# New_SERV_OPEN8_SOTB.net
KiCad netlist of a schematic drawn in EAGLE
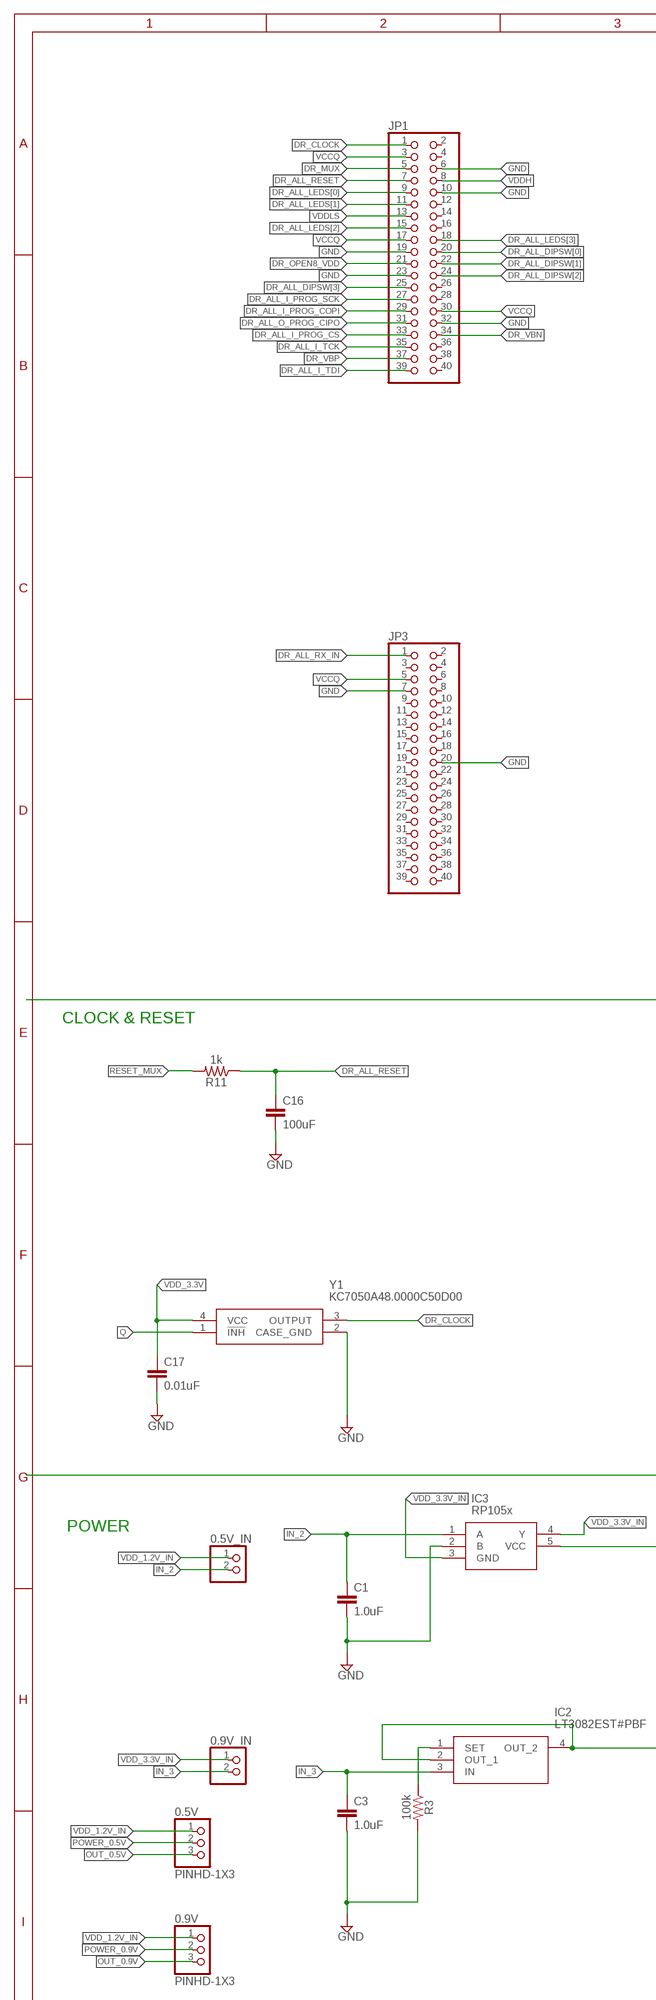
[diagram p0: schematic, sheet 1, part 1 of 2]
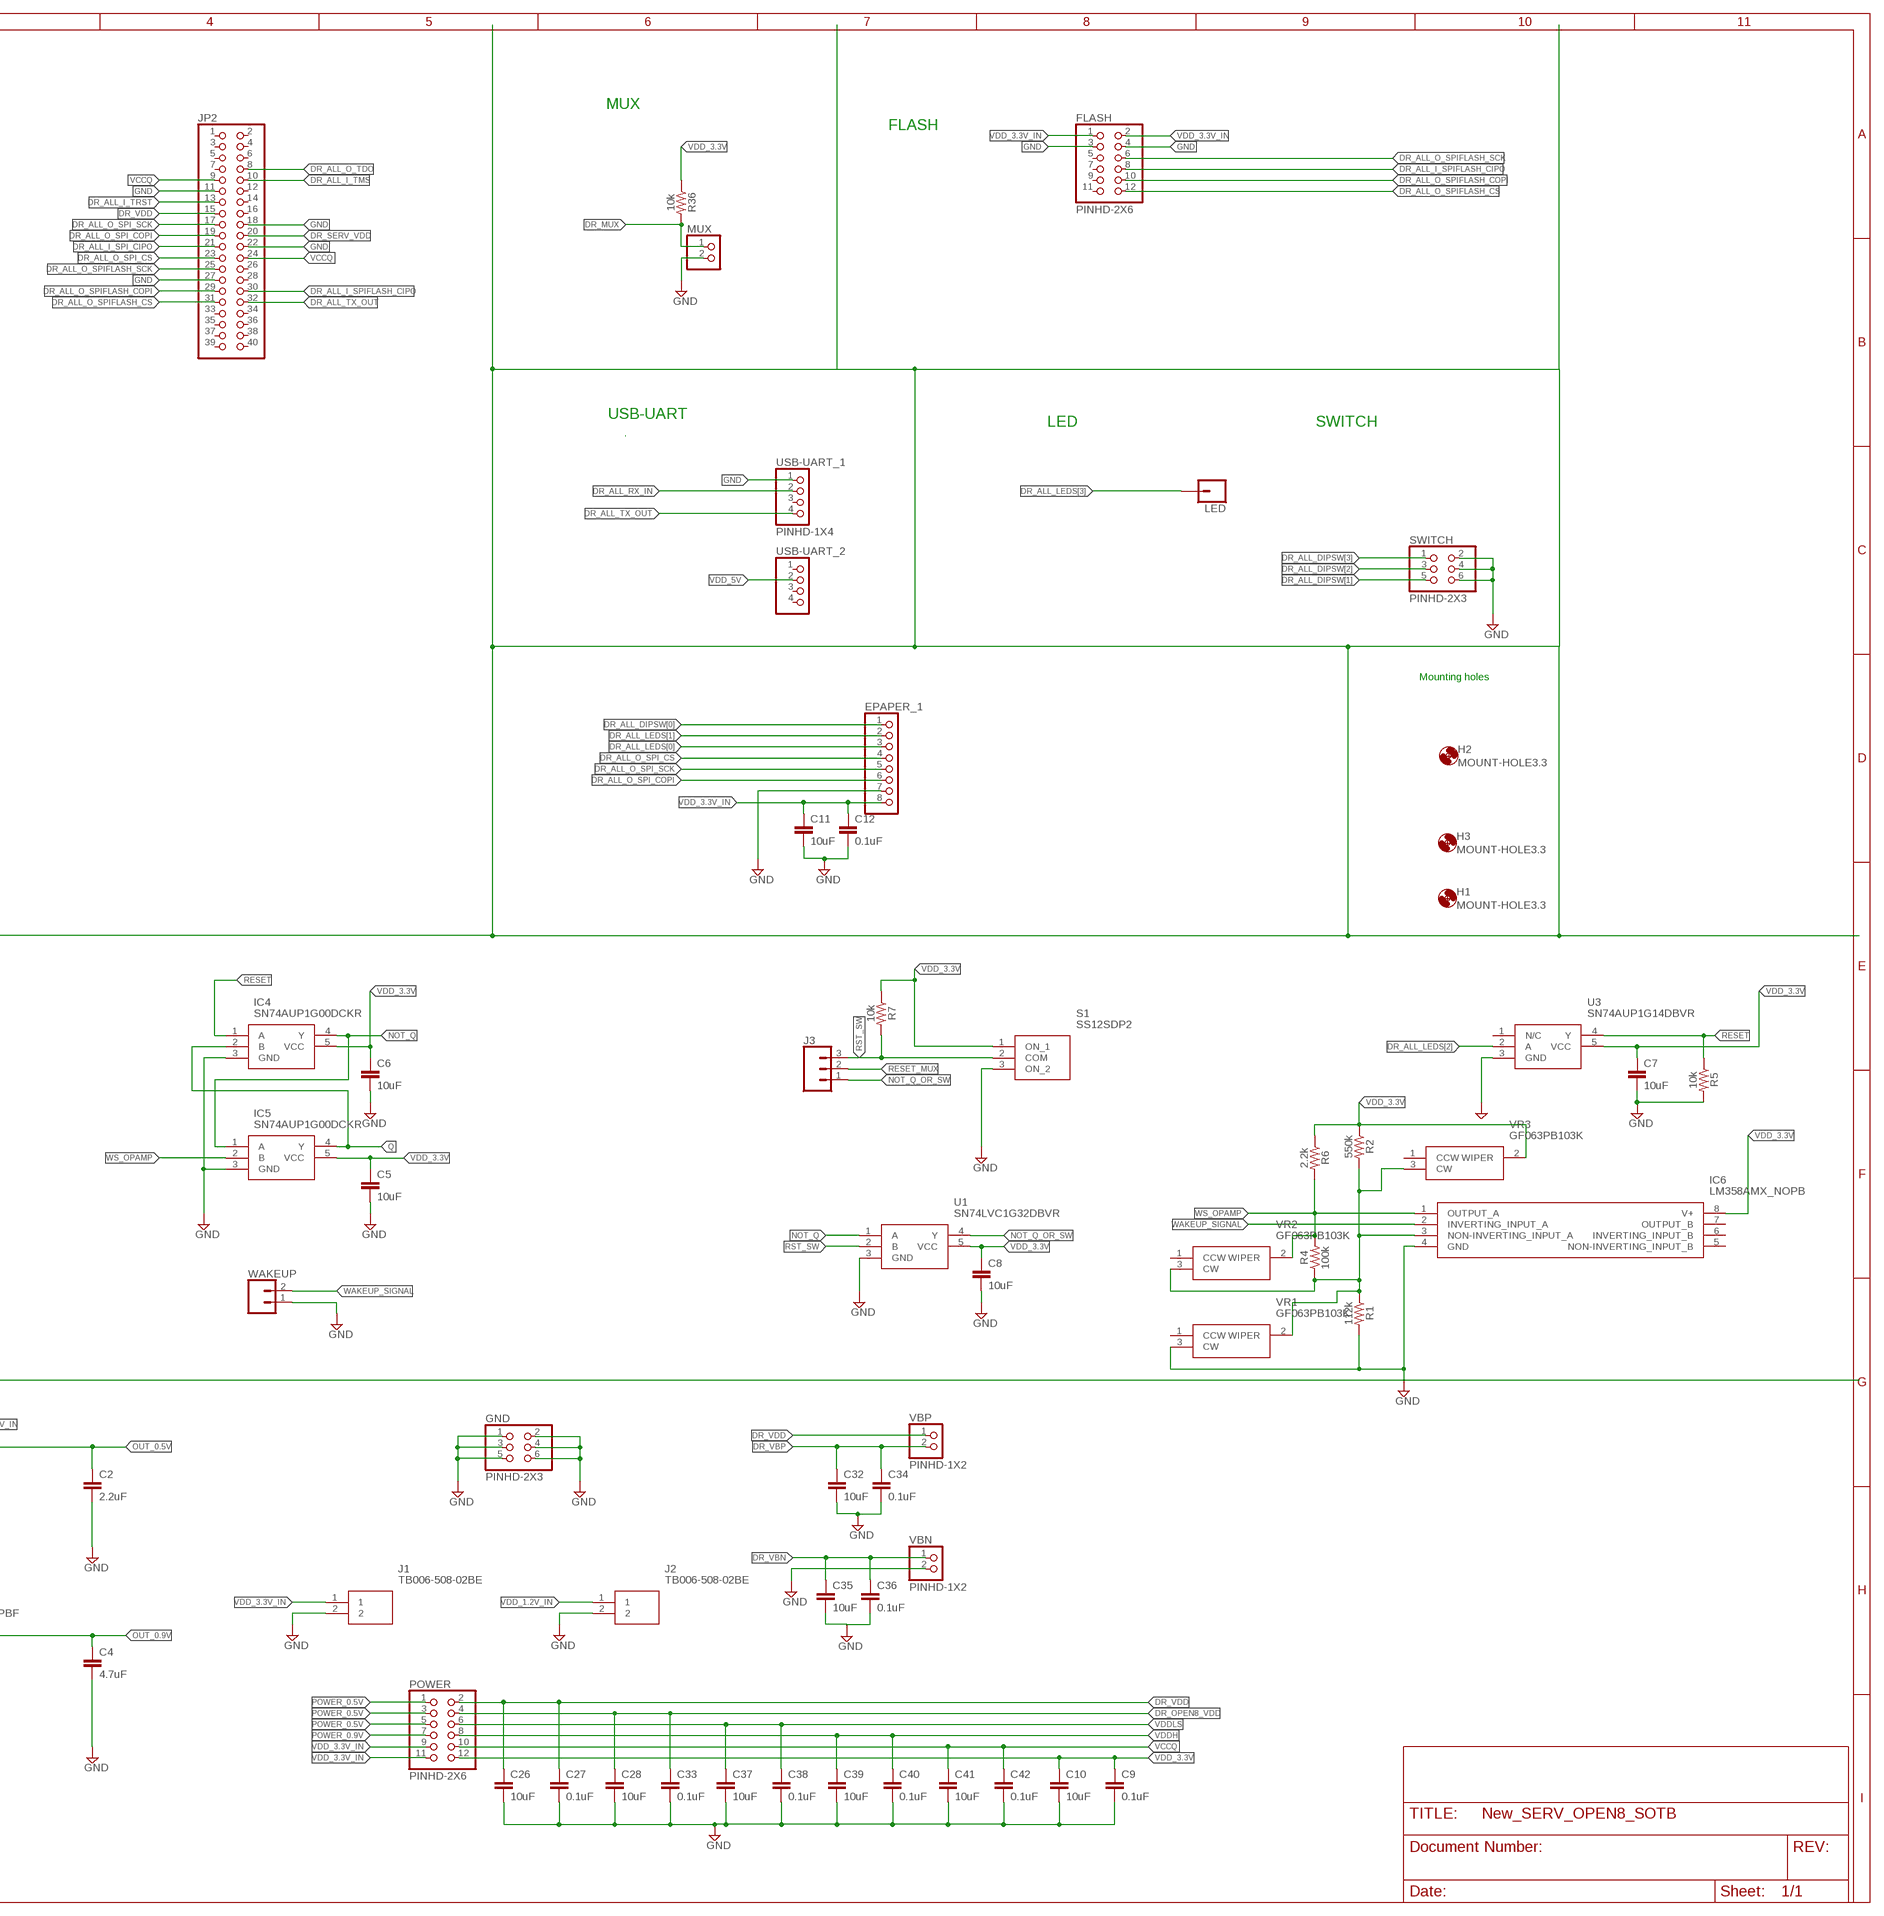
[diagram p1: schematic, sheet 1, part 2 of 2]

(export (version "E")
  (design (tool "Eeschema 10.0.6"))
  (components
    (comp (ref "0.5V")
      (value "PINHD-1X3")
      (footprint "eagle-import:1X03")
      (libsource (lib "eagle-import") (part "PINHD-1X3"))
    )
    (comp (ref "0.5V_IN")
      (value "PINHD-1X2")
      (footprint "eagle-import:1X02")
      (libsource (lib "eagle-import") (part "pinhead_325_PINHD-1X2"))
    )
    (comp (ref "0.9V")
      (value "PINHD-1X3")
      (footprint "eagle-import:1X03")
      (libsource (lib "eagle-import") (part "PINHD-1X3"))
    )
    (comp (ref "0.9V_IN")
      (value "PINHD-1X2")
      (footprint "eagle-import:1X02")
      (libsource (lib "eagle-import") (part "pinhead_325_PINHD-1X2"))
    )
    (comp (ref "C1")
      (value "1.0uF")
      (footprint "eagle-import:0805")
      (libsource (lib "eagle-import") (part "1.0UF-0805-25V-(+80/-20%)"))
    )
    (comp (ref "C2")
      (value "2.2uF")
      (footprint "eagle-import:0805")
      (libsource (lib "eagle-import") (part "1.0UF-0805-25V-(+80/-20%)"))
    )
    (comp (ref "C3")
      (value "1.0uF")
      (footprint "eagle-import:0805")
      (libsource (lib "eagle-import") (part "1.0UF-0805-25V-(+80/-20%)"))
    )
    (comp (ref "C4")
      (value "4.7uF")
      (footprint "eagle-import:0805")
      (libsource (lib "eagle-import") (part "1.0UF-0805-25V-(+80/-20%)"))
    )
    (comp (ref "C5")
      (value "10uF")
      (footprint "eagle-import:0805")
      (libsource (lib "eagle-import") (part "1.0UF-0805-25V-(+80/-20%)"))
    )
    (comp (ref "C6")
      (value "10uF")
      (footprint "eagle-import:0805")
      (libsource (lib "eagle-import") (part "1.0UF-0805-25V-(+80/-20%)"))
    )
    (comp (ref "C7")
      (value "10uF")
      (footprint "eagle-import:0805")
      (libsource (lib "eagle-import") (part "1.0UF-0805-25V-(+80/-20%)"))
    )
    (comp (ref "C8")
      (value "10uF")
      (footprint "eagle-import:0805")
      (libsource (lib "eagle-import") (part "1.0UF-0805-25V-(+80/-20%)"))
    )
    (comp (ref "C9")
      (value "0.1uF")
      (footprint "eagle-import:0805")
      (libsource (lib "eagle-import") (part "1.0UF-0805-25V-(+80/-20%)"))
    )
    (comp (ref "C10")
      (value "10uF")
      (footprint "eagle-import:0805")
      (libsource (lib "eagle-import") (part "1.0UF-0805-25V-(+80/-20%)"))
    )
    (comp (ref "C11")
      (value "10uF")
      (footprint "eagle-import:0805")
      (libsource (lib "eagle-import") (part "1.0UF-0805-25V-(+80/-20%)"))
    )
    (comp (ref "C12")
      (value "0.1uF")
      (footprint "eagle-import:0805")
      (libsource (lib "eagle-import") (part "1.0UF-0805-25V-(+80/-20%)"))
    )
    (comp (ref "C16")
      (value "100uF")
      (footprint "eagle-import:0805")
      (libsource (lib "eagle-import") (part "1.0UF-0805-25V-(+80/-20%)"))
    )
    (comp (ref "C17")
      (value "0.01uF")
      (footprint "eagle-import:0805")
      (libsource (lib "eagle-import") (part "1.0UF-0805-25V-(+80/-20%)"))
    )
    (comp (ref "C26")
      (value "10uF")
      (footprint "eagle-import:0805")
      (libsource (lib "eagle-import") (part "1.0UF-0805-25V-(+80/-20%)"))
    )
    (comp (ref "C27")
      (value "0.1uF")
      (footprint "eagle-import:0805")
      (libsource (lib "eagle-import") (part "1.0UF-0805-25V-(+80/-20%)"))
    )
    (comp (ref "C28")
      (value "10uF")
      (footprint "eagle-import:0805")
      (libsource (lib "eagle-import") (part "1.0UF-0805-25V-(+80/-20%)"))
    )
    (comp (ref "C32")
      (value "10uF")
      (footprint "eagle-import:0805")
      (libsource (lib "eagle-import") (part "1.0UF-0805-25V-(+80/-20%)"))
    )
    (comp (ref "C33")
      (value "0.1uF")
      (footprint "eagle-import:0805")
      (libsource (lib "eagle-import") (part "1.0UF-0805-25V-(+80/-20%)"))
    )
    (comp (ref "C34")
      (value "0.1uF")
      (footprint "eagle-import:0805")
      (libsource (lib "eagle-import") (part "1.0UF-0805-25V-(+80/-20%)"))
    )
    (comp (ref "C35")
      (value "10uF")
      (footprint "eagle-import:0805")
      (libsource (lib "eagle-import") (part "1.0UF-0805-25V-(+80/-20%)"))
    )
    (comp (ref "C36")
      (value "0.1uF")
      (footprint "eagle-import:0805")
      (libsource (lib "eagle-import") (part "1.0UF-0805-25V-(+80/-20%)"))
    )
    (comp (ref "C37")
      (value "10uF")
      (footprint "eagle-import:0805")
      (libsource (lib "eagle-import") (part "1.0UF-0805-25V-(+80/-20%)"))
    )
    (comp (ref "C38")
      (value "0.1uF")
      (footprint "eagle-import:0805")
      (libsource (lib "eagle-import") (part "1.0UF-0805-25V-(+80/-20%)"))
    )
    (comp (ref "C39")
      (value "10uF")
      (footprint "eagle-import:0805")
      (libsource (lib "eagle-import") (part "1.0UF-0805-25V-(+80/-20%)"))
    )
    (comp (ref "C40")
      (value "0.1uF")
      (footprint "eagle-import:0805")
      (libsource (lib "eagle-import") (part "1.0UF-0805-25V-(+80/-20%)"))
    )
    (comp (ref "C41")
      (value "10uF")
      (footprint "eagle-import:0805")
      (libsource (lib "eagle-import") (part "1.0UF-0805-25V-(+80/-20%)"))
    )
    (comp (ref "C42")
      (value "0.1uF")
      (footprint "eagle-import:0805")
      (libsource (lib "eagle-import") (part "1.0UF-0805-25V-(+80/-20%)"))
    )
    (comp (ref "EPAPER_1")
      (value "PINHD-1X8")
      (footprint "eagle-import:1X08")
      (libsource (lib "eagle-import") (part "PINHD-1X8"))
    )
    (comp (ref "FLASH")
      (value "PINHD-2X6")
      (footprint "eagle-import:2X06")
      (libsource (lib "eagle-import") (part "PINHD-2X6"))
    )
    (comp (ref "GND")
      (value "PINHD-2X3")
      (footprint "eagle-import:2X03")
      (libsource (lib "eagle-import") (part "PINHD-2X3"))
    )
    (comp (ref "H1")
      (value "MOUNT-HOLE3.3")
      (footprint "eagle-import:3,3")
      (libsource (lib "eagle-import") (part "MOUNT-HOLE3.3"))
    )
    (comp (ref "H2")
      (value "MOUNT-HOLE3.3")
      (footprint "eagle-import:3,3")
      (libsource (lib "eagle-import") (part "MOUNT-HOLE3.3"))
    )
    (comp (ref "H3")
      (value "MOUNT-HOLE3.3")
      (footprint "eagle-import:3,3")
      (libsource (lib "eagle-import") (part "MOUNT-HOLE3.3"))
    )
    (comp (ref "IC2")
      (value "LT3082EST#PBF")
      (footprint "eagle-import:SOT230P700X180-4N")
      (fields (field (name "MOUSER_PART_NUMBER") "584-LT3082EST#PBF"))
      (libsource (lib "eagle-import") (part "LT3082EST#PBF"))
    )
    (comp (ref "IC3")
      (value "RP105x")
      (footprint "eagle-import:SOT95P280X145-5N")
      (fields
        (field (name "ARROW_PART_NUMBER") "SN74LVC1G32DBVR")
        (field (name "MOUSER_PART_NUMBER") "595-SN74LVC1G32DBVR")
      )
      (libsource (lib "eagle-import") (part "SN74LVC1G32DBVR"))
    )
    (comp (ref "IC4")
      (value "SN74AUP1G00DCKR")
      (footprint "eagle-import:SOT65P210X110-5N")
      (fields (field (name "MOUSER_PART_NUMBER") "595-SN74AUP1G00DCKR"))
      (libsource (lib "eagle-import") (part "SN74AUP1G00DCKR"))
    )
    (comp (ref "IC5")
      (value "SN74AUP1G00DCKR")
      (footprint "eagle-import:SOT65P210X110-5N")
      (fields (field (name "MOUSER_PART_NUMBER") "595-SN74AUP1G00DCKR"))
      (libsource (lib "eagle-import") (part "SN74AUP1G00DCKR"))
    )
    (comp (ref "IC6")
      (value "LM358AMX_NOPB")
      (footprint "eagle-import:SOIC127P600X175-8N")
      (fields
        (field (name "ARROW_PART_NUMBER") "LM358AMX/NOPB")
        (field (name "MOUSER_PART_NUMBER") "926-LM358AMX/NOPB")
      )
      (libsource (lib "eagle-import") (part "LM358AMX_NOPB"))
    )
    (comp (ref "J1")
      (value "TB006-508-02BE")
      (footprint "eagle-import:TB00650802BE")
      (fields (field (name "MOUSER_PART_NUMBER") "490-TB006-508-02BE"))
      (libsource (lib "eagle-import") (part "TB006-508-02BE"))
    )
    (comp (ref "J2")
      (value "TB006-508-02BE")
      (footprint "eagle-import:TB00650802BE")
      (fields (field (name "MOUSER_PART_NUMBER") "490-TB006-508-02BE"))
      (libsource (lib "eagle-import") (part "TB006-508-02BE"))
    )
    (comp (ref "J3")
      (value "CONN_03")
      (footprint "eagle-import:1X03")
      (libsource (lib "eagle-import") (part "CONN_03"))
    )
    (comp (ref "JP1")
      (value "PINHD-2X20")
      (footprint "eagle-import:2X20")
      (libsource (lib "eagle-import") (part "PINHD-2X20"))
    )
    (comp (ref "JP2")
      (value "PINHD-2X20")
      (footprint "eagle-import:2X20")
      (libsource (lib "eagle-import") (part "PINHD-2X20"))
    )
    (comp (ref "JP3")
      (value "PINHD-2X20")
      (footprint "eagle-import:2X20")
      (libsource (lib "eagle-import") (part "PINHD-2X20"))
    )
    (comp (ref "LED")
      (value "CONN_01")
      (footprint "eagle-import:1X01")
      (libsource (lib "eagle-import") (part "CONN_01"))
    )
    (comp (ref "MUX")
      (value "PINHD-1X2")
      (footprint "eagle-import:1X02")
      (libsource (lib "eagle-import") (part "pinhead_325_PINHD-1X2"))
    )
    (comp (ref "POWER")
      (value "PINHD-2X6")
      (footprint "eagle-import:2X06")
      (libsource (lib "eagle-import") (part "PINHD-2X6"))
    )
    (comp (ref "R1")
      (value "112k")
      (footprint "eagle-import:0805")
      (libsource (lib "eagle-import") (part "0.3OHM-0805-1/8W-1%"))
    )
    (comp (ref "R2")
      (value "550k")
      (footprint "eagle-import:0805")
      (libsource (lib "eagle-import") (part "0.3OHM-0805-1/8W-1%"))
    )
    (comp (ref "R3")
      (value "100k")
      (footprint "eagle-import:0805")
      (libsource (lib "eagle-import") (part "0.3OHM-0805-1/8W-1%"))
    )
    (comp (ref "R4")
      (value "100k")
      (footprint "eagle-import:0805")
      (libsource (lib "eagle-import") (part "0.3OHM-0805-1/8W-1%"))
    )
    (comp (ref "R5")
      (value "10k")
      (footprint "eagle-import:0805")
      (libsource (lib "eagle-import") (part "0.3OHM-0805-1/8W-1%"))
    )
    (comp (ref "R6")
      (value "2.2k")
      (footprint "eagle-import:0805")
      (libsource (lib "eagle-import") (part "0.3OHM-0805-1/8W-1%"))
    )
    (comp (ref "R7")
      (value "10k")
      (footprint "eagle-import:0805")
      (libsource (lib "eagle-import") (part "0.3OHM-0805-1/8W-1%"))
    )
    (comp (ref "R11")
      (value "1k")
      (footprint "eagle-import:0805")
      (libsource (lib "eagle-import") (part "0.3OHM-0805-1/8W-1%"))
    )
    (comp (ref "R36")
      (value "10k")
      (footprint "eagle-import:0805")
      (libsource (lib "eagle-import") (part "0.3OHM-0805-1/8W-1%"))
    )
    (comp (ref "S1")
      (value "SS12SDP2")
      (footprint "eagle-import:SS12SDP2")
      (fields (field (name "MOUSER_PART_NUMBER") "633-SS12SDP2"))
      (libsource (lib "eagle-import") (part "SS12SDP2"))
    )
    (comp (ref "SWITCH")
      (value "PINHD-2X3")
      (footprint "eagle-import:2X03")
      (libsource (lib "eagle-import") (part "PINHD-2X3"))
    )
    (comp (ref "U1")
      (value "SN74LVC1G32DBVR")
      (footprint "eagle-import:SOT95P280X145-5N")
      (fields (field (name "MOUSER_PART_NUMBER") "595-SN74LVC1G32DBVR"))
      (libsource (lib "eagle-import") (part "SN74LVC1G32DBVR"))
    )
    (comp (ref "U3")
      (value "SN74AUP1G14DBVR")
      (footprint "eagle-import:SOT65P210X110-5N")
      (fields (field (name "MOUSER_PART_NUMBER") "595-SN74AUP1G14DBVR"))
      (libsource (lib "eagle-import") (part "SN74AUP1G14DBVR"))
    )
    (comp (ref "USB-UART_1")
      (value "PINHD-1X4")
      (footprint "eagle-import:1X04")
      (libsource (lib "eagle-import") (part "PINHD-1X4"))
    )
    (comp (ref "USB-UART_2")
      (value "PINHD-1X4")
      (footprint "eagle-import:1X04")
      (libsource (lib "eagle-import") (part "PINHD-1X4"))
    )
    (comp (ref "VBN")
      (value "PINHD-1X2")
      (footprint "eagle-import:1X02")
      (libsource (lib "eagle-import") (part "PINHD-1X2"))
    )
    (comp (ref "VBP")
      (value "PINHD-1X2")
      (footprint "eagle-import:1X02")
      (libsource (lib "eagle-import") (part "PINHD-1X2"))
    )
    (comp (ref "VR1")
      (value "GF063PB103K")
      (footprint "eagle-import:GF063PB103K")
      (libsource (lib "eagle-import") (part "GF063PB103K"))
    )
    (comp (ref "VR2")
      (value "GF063PB103K")
      (footprint "eagle-import:GF063PB103K")
      (libsource (lib "eagle-import") (part "GF063PB103K"))
    )
    (comp (ref "VR3")
      (value "GF063PB103K")
      (footprint "eagle-import:GF063PB103K")
      (libsource (lib "eagle-import") (part "GF063PB103K"))
    )
    (comp (ref "WAKEUP")
      (value "CONN_02")
      (footprint "eagle-import:1X02")
      (libsource (lib "eagle-import") (part "CONN_02"))
    )
    (comp (ref "Y1")
      (value "KC7050A48.0000C50D00")
      (footprint "eagle-import:KC7050A480000C50D00")
      (fields (field (name "MOUSER_PART_NUMBER") "581-KC7050A48C50D"))
      (libsource (lib "eagle-import") (part "KC7050A48.0000C50D00"))
    )
  )
  (nets
    (net (code "1") (name "DR_ALL_DIPSW[0]") (class "Default")
      (node (ref "EPAPER_1") (pin "1") (pinfunction "1_1") (pintype "passive"))
      (node (ref "JP1") (pin "20") (pinfunction "20_20") (pintype "passive"))
    )
    (net (code "2") (name "DR_ALL_DIPSW[1]") (class "Default")
      (node (ref "JP1") (pin "22") (pinfunction "22_22") (pintype "passive"))
      (node (ref "SWITCH") (pin "5") (pinfunction "5_5") (pintype "passive"))
    )
    (net (code "3") (name "DR_ALL_DIPSW[2]") (class "Default")
      (node (ref "JP1") (pin "24") (pinfunction "24_24") (pintype "passive"))
      (node (ref "SWITCH") (pin "3") (pinfunction "3_3") (pintype "passive"))
    )
    (net (code "4") (name "DR_ALL_DIPSW[3]") (class "Default")
      (node (ref "JP1") (pin "25") (pinfunction "25_25") (pintype "passive"))
      (node (ref "SWITCH") (pin "1") (pinfunction "1_1") (pintype "passive"))
    )
    (net (code "5") (name "DR_ALL_I_PROG_COPI") (class "Default")
      (node (ref "JP1") (pin "29") (pinfunction "29_29") (pintype "passive"))
    )
    (net (code "6") (name "DR_ALL_I_PROG_CS") (class "Default")
      (node (ref "JP1") (pin "33") (pinfunction "33_33") (pintype "passive"))
    )
    (net (code "7") (name "DR_ALL_I_PROG_SCK") (class "Default")
      (node (ref "JP1") (pin "27") (pinfunction "27_27") (pintype "passive"))
    )
    (net (code "8") (name "DR_ALL_I_SPIFLASH_CIPO") (class "Default")
      (node (ref "FLASH") (pin "8") (pinfunction "8_8") (pintype "passive"))
      (node (ref "JP2") (pin "30") (pinfunction "30_30") (pintype "passive"))
    )
    (net (code "9") (name "DR_ALL_I_SPI_CIPO") (class "Default")
      (node (ref "JP2") (pin "21") (pinfunction "21_21") (pintype "passive"))
    )
    (net (code "10") (name "DR_ALL_I_TCK") (class "Default")
      (node (ref "JP1") (pin "35") (pinfunction "35_35") (pintype "passive"))
    )
    (net (code "11") (name "DR_ALL_I_TDI") (class "Default")
      (node (ref "JP1") (pin "39") (pinfunction "39_39") (pintype "passive"))
    )
    (net (code "12") (name "DR_ALL_I_TMS") (class "Default")
      (node (ref "JP2") (pin "10") (pinfunction "10_10") (pintype "passive"))
    )
    (net (code "13") (name "DR_ALL_I_TRST") (class "Default")
      (node (ref "JP2") (pin "13") (pinfunction "13_13") (pintype "passive"))
    )
    (net (code "14") (name "DR_ALL_LEDS[0]") (class "Default")
      (node (ref "EPAPER_1") (pin "3") (pinfunction "3_3") (pintype "passive"))
      (node (ref "JP1") (pin "9") (pinfunction "9_9") (pintype "passive"))
    )
    (net (code "15") (name "DR_ALL_LEDS[1]") (class "Default")
      (node (ref "EPAPER_1") (pin "2") (pinfunction "2_2") (pintype "passive"))
      (node (ref "JP1") (pin "11") (pinfunction "11_11") (pintype "passive"))
    )
    (net (code "16") (name "DR_ALL_LEDS[2]") (class "Default")
      (node (ref "JP1") (pin "15") (pinfunction "15_15") (pintype "passive"))
      (node (ref "U3") (pin "2") (pinfunction "A_2") (pintype "input"))
    )
    (net (code "17") (name "DR_ALL_LEDS[3]") (class "Default")
      (node (ref "JP1") (pin "18") (pinfunction "18_18") (pintype "passive"))
      (node (ref "LED") (pin "1") (pinfunction "1_1") (pintype "passive"))
    )
    (net (code "18") (name "DR_ALL_O_PROG_CIPO") (class "Default")
      (node (ref "JP1") (pin "31") (pinfunction "31_31") (pintype "passive"))
    )
    (net (code "19") (name "DR_ALL_O_SPIFLASH_COPI") (class "Default")
      (node (ref "FLASH") (pin "10") (pinfunction "10_10") (pintype "passive"))
      (node (ref "JP2") (pin "29") (pinfunction "29_29") (pintype "passive"))
    )
    (net (code "20") (name "DR_ALL_O_SPIFLASH_CS") (class "Default")
      (node (ref "FLASH") (pin "12") (pinfunction "12_12") (pintype "passive"))
      (node (ref "JP2") (pin "31") (pinfunction "31_31") (pintype "passive"))
    )
    (net (code "21") (name "DR_ALL_O_SPIFLASH_SCK") (class "Default")
      (node (ref "FLASH") (pin "6") (pinfunction "6_6") (pintype "passive"))
      (node (ref "JP2") (pin "25") (pinfunction "25_25") (pintype "passive"))
    )
    (net (code "22") (name "DR_ALL_O_SPI_COPI") (class "Default")
      (node (ref "EPAPER_1") (pin "6") (pinfunction "6_6") (pintype "passive"))
      (node (ref "JP2") (pin "19") (pinfunction "19_19") (pintype "passive"))
    )
    (net (code "23") (name "DR_ALL_O_SPI_CS") (class "Default")
      (node (ref "EPAPER_1") (pin "4") (pinfunction "4_4") (pintype "passive"))
      (node (ref "JP2") (pin "23") (pinfunction "23_23") (pintype "passive"))
    )
    (net (code "24") (name "DR_ALL_O_SPI_SCK") (class "Default")
      (node (ref "EPAPER_1") (pin "5") (pinfunction "5_5") (pintype "passive"))
      (node (ref "JP2") (pin "17") (pinfunction "17_17") (pintype "passive"))
    )
    (net (code "25") (name "DR_ALL_O_TDO") (class "Default")
      (node (ref "JP2") (pin "8") (pinfunction "8_8") (pintype "passive"))
    )
    (net (code "26") (name "DR_ALL_RESET") (class "Default")
      (node (ref "C16") (pin "1") (pinfunction "1_1") (pintype "passive"))
      (node (ref "JP1") (pin "7") (pinfunction "7_7") (pintype "passive"))
      (node (ref "R11") (pin "1") (pinfunction "1_1") (pintype "passive"))
    )
    (net (code "27") (name "DR_ALL_RX_IN") (class "Default")
      (node (ref "JP3") (pin "1") (pinfunction "1_1") (pintype "passive"))
      (node (ref "USB-UART_1") (pin "2") (pinfunction "2_2") (pintype "passive"))
    )
    (net (code "28") (name "DR_ALL_TX_OUT") (class "Default")
      (node (ref "JP2") (pin "32") (pinfunction "32_32") (pintype "passive"))
      (node (ref "USB-UART_1") (pin "4") (pinfunction "4_4") (pintype "passive"))
    )
    (net (code "29") (name "DR_CLOCK") (class "Default")
      (node (ref "JP1") (pin "1") (pinfunction "1_1") (pintype "passive"))
      (node (ref "Y1") (pin "3") (pinfunction "OUTPUT_3") (pintype "bidirectional"))
    )
    (net (code "30") (name "DR_MUX") (class "Default")
      (node (ref "JP1") (pin "5") (pinfunction "5_5") (pintype "passive"))
      (node (ref "MUX") (pin "1") (pinfunction "1_1") (pintype "passive"))
      (node (ref "R36") (pin "2") (pinfunction "2_2") (pintype "passive"))
    )
    (net (code "31") (name "DR_OPEN8_VDD") (class "Default")
      (node (ref "C28") (pin "1") (pinfunction "1_1") (pintype "passive"))
      (node (ref "C33") (pin "1") (pinfunction "1_1") (pintype "passive"))
      (node (ref "JP1") (pin "21") (pinfunction "21_21") (pintype "passive"))
      (node (ref "POWER") (pin "4") (pinfunction "4_4") (pintype "passive"))
    )
    (net (code "32") (name "DR_SERV_VDD") (class "Default")
      (node (ref "JP2") (pin "20") (pinfunction "20_20") (pintype "passive"))
    )
    (net (code "33") (name "DR_VBN") (class "Default")
      (node (ref "C35") (pin "1") (pinfunction "1_1") (pintype "passive"))
      (node (ref "C36") (pin "1") (pinfunction "1_1") (pintype "passive"))
      (node (ref "JP1") (pin "34") (pinfunction "34_34") (pintype "passive"))
      (node (ref "VBN") (pin "1") (pinfunction "1_1") (pintype "passive"))
    )
    (net (code "34") (name "DR_VBP") (class "Default")
      (node (ref "C32") (pin "1") (pinfunction "1_1") (pintype "passive"))
      (node (ref "C34") (pin "1") (pinfunction "1_1") (pintype "passive"))
      (node (ref "JP1") (pin "37") (pinfunction "37_37") (pintype "passive"))
      (node (ref "VBP") (pin "2") (pinfunction "2_2") (pintype "passive"))
    )
    (net (code "35") (name "DR_VDD") (class "Default")
      (node (ref "C26") (pin "1") (pinfunction "1_1") (pintype "passive"))
      (node (ref "C27") (pin "1") (pinfunction "1_1") (pintype "passive"))
      (node (ref "JP2") (pin "15") (pinfunction "15_15") (pintype "passive"))
      (node (ref "POWER") (pin "2") (pinfunction "2_2") (pintype "passive"))
      (node (ref "VBP") (pin "1") (pinfunction "1_1") (pintype "passive"))
    )
    (net (code "36") (name "GND") (class "Default")
      (node (ref "C1") (pin "2") (pinfunction "2_2") (pintype "passive"))
      (node (ref "C10") (pin "2") (pinfunction "2_2") (pintype "passive"))
      (node (ref "C11") (pin "2") (pinfunction "2_2") (pintype "passive"))
      (node (ref "C12") (pin "2") (pinfunction "2_2") (pintype "passive"))
      (node (ref "C16") (pin "2") (pinfunction "2_2") (pintype "passive"))
      (node (ref "C17") (pin "2") (pinfunction "2_2") (pintype "passive"))
      (node (ref "C2") (pin "2") (pinfunction "2_2") (pintype "passive"))
      (node (ref "C26") (pin "2") (pinfunction "2_2") (pintype "passive"))
      (node (ref "C27") (pin "2") (pinfunction "2_2") (pintype "passive"))
      (node (ref "C28") (pin "2") (pinfunction "2_2") (pintype "passive"))
      (node (ref "C3") (pin "2") (pinfunction "2_2") (pintype "passive"))
      (node (ref "C32") (pin "2") (pinfunction "2_2") (pintype "passive"))
      (node (ref "C33") (pin "2") (pinfunction "2_2") (pintype "passive"))
      (node (ref "C34") (pin "2") (pinfunction "2_2") (pintype "passive"))
      (node (ref "C35") (pin "2") (pinfunction "2_2") (pintype "passive"))
      (node (ref "C36") (pin "2") (pinfunction "2_2") (pintype "passive"))
      (node (ref "C37") (pin "2") (pinfunction "2_2") (pintype "passive"))
      (node (ref "C38") (pin "2") (pinfunction "2_2") (pintype "passive"))
      (node (ref "C39") (pin "2") (pinfunction "2_2") (pintype "passive"))
      (node (ref "C4") (pin "2") (pinfunction "2_2") (pintype "passive"))
      (node (ref "C40") (pin "2") (pinfunction "2_2") (pintype "passive"))
      (node (ref "C41") (pin "2") (pinfunction "2_2") (pintype "passive"))
      (node (ref "C42") (pin "2") (pinfunction "2_2") (pintype "passive"))
      (node (ref "C5") (pin "2") (pinfunction "2_2") (pintype "passive"))
      (node (ref "C6") (pin "2") (pinfunction "2_2") (pintype "passive"))
      (node (ref "C7") (pin "2") (pinfunction "2_2") (pintype "passive"))
      (node (ref "C8") (pin "2") (pinfunction "2_2") (pintype "passive"))
      (node (ref "C9") (pin "2") (pinfunction "2_2") (pintype "passive"))
      (node (ref "EPAPER_1") (pin "7") (pinfunction "7_7") (pintype "passive"))
      (node (ref "FLASH") (pin "3") (pinfunction "3_3") (pintype "passive"))
      (node (ref "FLASH") (pin "4") (pinfunction "4_4") (pintype "passive"))
      (node (ref "GND") (pin "1") (pinfunction "1_1") (pintype "passive"))
      (node (ref "GND") (pin "2") (pinfunction "2_2") (pintype "passive"))
      (node (ref "GND") (pin "3") (pinfunction "3_3") (pintype "passive"))
      (node (ref "GND") (pin "4") (pinfunction "4_4") (pintype "passive"))
      (node (ref "GND") (pin "5") (pinfunction "5_5") (pintype "passive"))
      (node (ref "GND") (pin "6") (pinfunction "6_6") (pintype "passive"))
      (node (ref "IC3") (pin "2") (pinfunction "B_2") (pintype "bidirectional"))
      (node (ref "IC4") (pin "3") (pinfunction "GND_3") (pintype "bidirectional"))
      (node (ref "IC5") (pin "3") (pinfunction "GND_3") (pintype "bidirectional"))
      (node (ref "IC6") (pin "4") (pinfunction "GND_4") (pintype "bidirectional"))
      (node (ref "J1") (pin "2") (pinfunction "2_2") (pintype "bidirectional"))
      (node (ref "J2") (pin "2") (pinfunction "2_2") (pintype "bidirectional"))
      (node (ref "JP1") (pin "10") (pinfunction "10_10") (pintype "passive"))
      (node (ref "JP1") (pin "19") (pinfunction "19_19") (pintype "passive"))
      (node (ref "JP1") (pin "23") (pinfunction "23_23") (pintype "passive"))
      (node (ref "JP1") (pin "32") (pinfunction "32_32") (pintype "passive"))
      (node (ref "JP1") (pin "6") (pinfunction "6_6") (pintype "passive"))
      (node (ref "JP2") (pin "11") (pinfunction "11_11") (pintype "passive"))
      (node (ref "JP2") (pin "18") (pinfunction "18_18") (pintype "passive"))
      (node (ref "JP2") (pin "22") (pinfunction "22_22") (pintype "passive"))
      (node (ref "JP2") (pin "27") (pinfunction "27_27") (pintype "passive"))
      (node (ref "JP3") (pin "20") (pinfunction "20_20") (pintype "passive"))
      (node (ref "JP3") (pin "7") (pinfunction "7_7") (pintype "passive"))
      (node (ref "MUX") (pin "2") (pinfunction "2_2") (pintype "passive"))
      (node (ref "R1") (pin "2") (pinfunction "2_2") (pintype "passive"))
      (node (ref "R3") (pin "2") (pinfunction "2_2") (pintype "passive"))
      (node (ref "R5") (pin "2") (pinfunction "2_2") (pintype "passive"))
      (node (ref "S1") (pin "3") (pinfunction "ON_2_3") (pintype "bidirectional"))
      (node (ref "SWITCH") (pin "2") (pinfunction "2_2") (pintype "passive"))
      (node (ref "SWITCH") (pin "4") (pinfunction "4_4") (pintype "passive"))
      (node (ref "SWITCH") (pin "6") (pinfunction "6_6") (pintype "passive"))
      (node (ref "U1") (pin "3") (pinfunction "GND_3") (pintype "bidirectional"))
      (node (ref "U3") (pin "3") (pinfunction "GND_3") (pintype "power_in"))
      (node (ref "USB-UART_1") (pin "1") (pinfunction "1_1") (pintype "passive"))
      (node (ref "VBN") (pin "2") (pinfunction "2_2") (pintype "passive"))
      (node (ref "VR1") (pin "3") (pinfunction "CW_3") (pintype "bidirectional"))
      (node (ref "WAKEUP") (pin "1") (pinfunction "1_1") (pintype "passive"))
      (node (ref "Y1") (pin "2") (pinfunction "CASE_GND_2") (pintype "bidirectional"))
    )
    (net (code "37") (name "IN_2") (class "Default")
      (node (ref "0.5V_IN") (pin "2") (pinfunction "2_2") (pintype "passive"))
      (node (ref "C1") (pin "1") (pinfunction "1_1") (pintype "passive"))
      (node (ref "IC3") (pin "1") (pinfunction "A_1") (pintype "bidirectional"))
    )
    (net (code "38") (name "IN_3") (class "Default")
      (node (ref "0.9V_IN") (pin "2") (pinfunction "2_2") (pintype "passive"))
      (node (ref "C3") (pin "1") (pinfunction "1_1") (pintype "passive"))
      (node (ref "IC2") (pin "3") (pinfunction "IN_3") (pintype "bidirectional"))
    )
    (net (code "39") (name "NOT_Q") (class "Default")
      (node (ref "IC4") (pin "4") (pinfunction "Y_4") (pintype "bidirectional"))
      (node (ref "IC5") (pin "1") (pinfunction "A_1") (pintype "bidirectional"))
      (node (ref "U1") (pin "1") (pinfunction "A_1") (pintype "bidirectional"))
    )
    (net (code "40") (name "NOT_Q_OR_SW") (class "Default")
      (node (ref "J3") (pin "1") (pinfunction "1_1") (pintype "passive"))
      (node (ref "U1") (pin "4") (pinfunction "Y_4") (pintype "bidirectional"))
    )
    (net (code "41") (name "Net-(IC2-SET)") (class "Default")
      (node (ref "IC2") (pin "1") (pinfunction "SET_1") (pintype "bidirectional"))
      (node (ref "R3") (pin "1") (pinfunction "1_1") (pintype "passive"))
    )
    (net (code "42") (name "Net-(IC6-NON-INVERTING_INPUT_A)") (class "Default")
      (node (ref "IC6") (pin "3") (pinfunction "NON-INVERTING_INPUT_A_3") (pintype "bidirectional"))
      (node (ref "R1") (pin "1") (pinfunction "1_1") (pintype "passive"))
      (node (ref "R2") (pin "2") (pinfunction "2_2") (pintype "passive"))
      (node (ref "R4") (pin "1") (pinfunction "1_1") (pintype "passive"))
      (node (ref "VR1") (pin "2") (pinfunction "WIPER_2") (pintype "bidirectional"))
      (node (ref "VR2") (pin "3") (pinfunction "CW_3") (pintype "bidirectional"))
      (node (ref "VR3") (pin "3") (pinfunction "CW_3") (pintype "bidirectional"))
    )
    (net (code "43") (name "OUT_0.5V") (class "Default")
      (node (ref "0.5V") (pin "3") (pinfunction "3_3") (pintype "passive"))
      (node (ref "C2") (pin "1") (pinfunction "1_1") (pintype "passive"))
      (node (ref "IC3") (pin "5") (pinfunction "VCC_5") (pintype "bidirectional"))
    )
    (net (code "44") (name "OUT_0.9V") (class "Default")
      (node (ref "0.9V") (pin "3") (pinfunction "3_3") (pintype "passive"))
      (node (ref "C4") (pin "1") (pinfunction "1_1") (pintype "passive"))
      (node (ref "IC2") (pin "2") (pinfunction "OUT_1_2") (pintype "bidirectional"))
      (node (ref "IC2") (pin "4") (pinfunction "OUT_2_4") (pintype "bidirectional"))
    )
    (net (code "45") (name "POWER_0.5V") (class "Default")
      (node (ref "0.5V") (pin "2") (pinfunction "2_2") (pintype "passive"))
      (node (ref "POWER") (pin "1") (pinfunction "1_1") (pintype "passive"))
      (node (ref "POWER") (pin "3") (pinfunction "3_3") (pintype "passive"))
      (node (ref "POWER") (pin "5") (pinfunction "5_5") (pintype "passive"))
    )
    (net (code "46") (name "POWER_0.9V") (class "Default")
      (node (ref "0.9V") (pin "2") (pinfunction "2_2") (pintype "passive"))
      (node (ref "POWER") (pin "7") (pinfunction "7_7") (pintype "passive"))
    )
    (net (code "47") (name "Q") (class "Default")
      (node (ref "IC4") (pin "2") (pinfunction "B_2") (pintype "bidirectional"))
      (node (ref "IC5") (pin "4") (pinfunction "Y_4") (pintype "bidirectional"))
      (node (ref "Y1") (pin "1") (pinfunction "~{INH}_1") (pintype "bidirectional"))
    )
    (net (code "48") (name "RESET") (class "Default")
      (node (ref "IC4") (pin "1") (pinfunction "A_1") (pintype "bidirectional"))
      (node (ref "R5") (pin "1") (pinfunction "1_1") (pintype "passive"))
      (node (ref "U3") (pin "4") (pinfunction "Y_4") (pintype "output"))
    )
    (net (code "49") (name "RESET_MUX") (class "Default")
      (node (ref "J3") (pin "2") (pinfunction "2_2") (pintype "passive"))
      (node (ref "R11") (pin "2") (pinfunction "2_2") (pintype "passive"))
    )
    (net (code "50") (name "RST_SW") (class "Default")
      (node (ref "J3") (pin "3") (pinfunction "3_3") (pintype "passive"))
      (node (ref "R7") (pin "2") (pinfunction "2_2") (pintype "passive"))
      (node (ref "S1") (pin "2") (pinfunction "COM_2") (pintype "bidirectional"))
      (node (ref "U1") (pin "2") (pinfunction "B_2") (pintype "bidirectional"))
    )
    (net (code "51") (name "VCCQ") (class "Default")
      (node (ref "C41") (pin "1") (pinfunction "1_1") (pintype "passive"))
      (node (ref "C42") (pin "1") (pinfunction "1_1") (pintype "passive"))
      (node (ref "JP1") (pin "17") (pinfunction "17_17") (pintype "passive"))
      (node (ref "JP1") (pin "3") (pinfunction "3_3") (pintype "passive"))
      (node (ref "JP1") (pin "30") (pinfunction "30_30") (pintype "passive"))
      (node (ref "JP2") (pin "24") (pinfunction "24_24") (pintype "passive"))
      (node (ref "JP2") (pin "9") (pinfunction "9_9") (pintype "passive"))
      (node (ref "JP3") (pin "5") (pinfunction "5_5") (pintype "passive"))
      (node (ref "POWER") (pin "10") (pinfunction "10_10") (pintype "passive"))
    )
    (net (code "52") (name "VDDH") (class "Default")
      (node (ref "C39") (pin "1") (pinfunction "1_1") (pintype "passive"))
      (node (ref "C40") (pin "1") (pinfunction "1_1") (pintype "passive"))
      (node (ref "JP1") (pin "8") (pinfunction "8_8") (pintype "passive"))
      (node (ref "POWER") (pin "8") (pinfunction "8_8") (pintype "passive"))
    )
    (net (code "53") (name "VDDLS") (class "Default")
      (node (ref "C37") (pin "1") (pinfunction "1_1") (pintype "passive"))
      (node (ref "C38") (pin "1") (pinfunction "1_1") (pintype "passive"))
      (node (ref "JP1") (pin "13") (pinfunction "13_13") (pintype "passive"))
      (node (ref "POWER") (pin "6") (pinfunction "6_6") (pintype "passive"))
    )
    (net (code "54") (name "VDD_1.2V_IN") (class "Default")
      (node (ref "0.5V") (pin "1") (pinfunction "1_1") (pintype "passive"))
      (node (ref "0.5V_IN") (pin "1") (pinfunction "1_1") (pintype "passive"))
      (node (ref "0.9V") (pin "1") (pinfunction "1_1") (pintype "passive"))
      (node (ref "J2") (pin "1") (pinfunction "1_1") (pintype "bidirectional"))
    )
    (net (code "55") (name "VDD_3.3V") (class "Default")
      (node (ref "C10") (pin "1") (pinfunction "1_1") (pintype "passive"))
      (node (ref "C17") (pin "1") (pinfunction "1_1") (pintype "passive"))
      (node (ref "C5") (pin "1") (pinfunction "1_1") (pintype "passive"))
      (node (ref "C6") (pin "1") (pinfunction "1_1") (pintype "passive"))
      (node (ref "C7") (pin "1") (pinfunction "1_1") (pintype "passive"))
      (node (ref "C8") (pin "1") (pinfunction "1_1") (pintype "passive"))
      (node (ref "C9") (pin "1") (pinfunction "1_1") (pintype "passive"))
      (node (ref "IC4") (pin "5") (pinfunction "VCC_5") (pintype "bidirectional"))
      (node (ref "IC5") (pin "5") (pinfunction "VCC_5") (pintype "bidirectional"))
      (node (ref "IC6") (pin "8") (pinfunction "V+_8") (pintype "bidirectional"))
      (node (ref "POWER") (pin "12") (pinfunction "12_12") (pintype "passive"))
      (node (ref "R2") (pin "1") (pinfunction "1_1") (pintype "passive"))
      (node (ref "R36") (pin "1") (pinfunction "1_1") (pintype "passive"))
      (node (ref "R6") (pin "1") (pinfunction "1_1") (pintype "passive"))
      (node (ref "R7") (pin "1") (pinfunction "1_1") (pintype "passive"))
      (node (ref "S1") (pin "1") (pinfunction "ON_1_1") (pintype "bidirectional"))
      (node (ref "U1") (pin "5") (pinfunction "VCC_5") (pintype "bidirectional"))
      (node (ref "U3") (pin "5") (pinfunction "VCC_5") (pintype "power_in"))
      (node (ref "VR3") (pin "2") (pinfunction "WIPER_2") (pintype "bidirectional"))
      (node (ref "Y1") (pin "4") (pinfunction "VCC_4") (pintype "bidirectional"))
    )
    (net (code "56") (name "VDD_3.3V_IN") (class "Default")
      (node (ref "0.9V_IN") (pin "1") (pinfunction "1_1") (pintype "passive"))
      (node (ref "C11") (pin "1") (pinfunction "1_1") (pintype "passive"))
      (node (ref "C12") (pin "1") (pinfunction "1_1") (pintype "passive"))
      (node (ref "EPAPER_1") (pin "8") (pinfunction "8_8") (pintype "passive"))
      (node (ref "FLASH") (pin "1") (pinfunction "1_1") (pintype "passive"))
      (node (ref "FLASH") (pin "2") (pinfunction "2_2") (pintype "passive"))
      (node (ref "IC3") (pin "3") (pinfunction "GND_3") (pintype "bidirectional"))
      (node (ref "IC3") (pin "4") (pinfunction "Y_4") (pintype "bidirectional"))
      (node (ref "J1") (pin "1") (pinfunction "1_1") (pintype "bidirectional"))
      (node (ref "POWER") (pin "11") (pinfunction "11_11") (pintype "passive"))
      (node (ref "POWER") (pin "9") (pinfunction "9_9") (pintype "passive"))
    )
    (net (code "57") (name "VDD_5V") (class "Default")
      (node (ref "USB-UART_2") (pin "2") (pinfunction "2_2") (pintype "passive"))
    )
    (net (code "58") (name "WAKEUP_SIGNAL") (class "Default")
      (node (ref "IC6") (pin "2") (pinfunction "INVERTING_INPUT_A_2") (pintype "bidirectional"))
      (node (ref "WAKEUP") (pin "2") (pinfunction "2_2") (pintype "passive"))
    )
    (net (code "59") (name "WS_OPAMP") (class "Default")
      (node (ref "IC5") (pin "2") (pinfunction "B_2") (pintype "bidirectional"))
      (node (ref "IC6") (pin "1") (pinfunction "OUTPUT_A_1") (pintype "bidirectional"))
      (node (ref "R4") (pin "2") (pinfunction "2_2") (pintype "passive"))
      (node (ref "R6") (pin "2") (pinfunction "2_2") (pintype "passive"))
      (node (ref "VR2") (pin "2") (pinfunction "WIPER_2") (pintype "bidirectional"))
    )
    (net (code "60") (name "unconnected-(FLASH-Pad5)") (class "Default")
      (node (ref "FLASH") (pin "5") (pinfunction "5_5") (pintype "passive"))
    )
    (net (code "61") (name "unconnected-(FLASH-Pad7)") (class "Default")
      (node (ref "FLASH") (pin "7") (pinfunction "7_7") (pintype "passive"))
    )
    (net (code "62") (name "unconnected-(FLASH-Pad9)") (class "Default")
      (node (ref "FLASH") (pin "9") (pinfunction "9_9") (pintype "passive"))
    )
    (net (code "63") (name "unconnected-(FLASH-Pad11)") (class "Default")
      (node (ref "FLASH") (pin "11") (pinfunction "11_11") (pintype "passive"))
    )
    (net (code "64") (name "unconnected-(IC6-INVERTING_INPUT_B-Pad6)") (class "Default")
      (node (ref "IC6") (pin "6") (pinfunction "INVERTING_INPUT_B_6") (pintype "bidirectional"))
    )
    (net (code "65") (name "unconnected-(IC6-NON-INVERTING_INPUT_B-Pad5)") (class "Default")
      (node (ref "IC6") (pin "5") (pinfunction "NON-INVERTING_INPUT_B_5") (pintype "bidirectional"))
    )
    (net (code "66") (name "unconnected-(IC6-OUTPUT_B-Pad7)") (class "Default")
      (node (ref "IC6") (pin "7") (pinfunction "OUTPUT_B_7") (pintype "bidirectional"))
    )
    (net (code "67") (name "unconnected-(JP1-Pad2)") (class "Default")
      (node (ref "JP1") (pin "2") (pinfunction "2_2") (pintype "passive"))
    )
    (net (code "68") (name "unconnected-(JP1-Pad4)") (class "Default")
      (node (ref "JP1") (pin "4") (pinfunction "4_4") (pintype "passive"))
    )
    (net (code "69") (name "unconnected-(JP1-Pad12)") (class "Default")
      (node (ref "JP1") (pin "12") (pinfunction "12_12") (pintype "passive"))
    )
    (net (code "70") (name "unconnected-(JP1-Pad14)") (class "Default")
      (node (ref "JP1") (pin "14") (pinfunction "14_14") (pintype "passive"))
    )
    (net (code "71") (name "unconnected-(JP1-Pad16)") (class "Default")
      (node (ref "JP1") (pin "16") (pinfunction "16_16") (pintype "passive"))
    )
    (net (code "72") (name "unconnected-(JP1-Pad26)") (class "Default")
      (node (ref "JP1") (pin "26") (pinfunction "26_26") (pintype "passive"))
    )
    (net (code "73") (name "unconnected-(JP1-Pad28)") (class "Default")
      (node (ref "JP1") (pin "28") (pinfunction "28_28") (pintype "passive"))
    )
    (net (code "74") (name "unconnected-(JP1-Pad36)") (class "Default")
      (node (ref "JP1") (pin "36") (pinfunction "36_36") (pintype "passive"))
    )
    (net (code "75") (name "unconnected-(JP1-Pad38)") (class "Default")
      (node (ref "JP1") (pin "38") (pinfunction "38_38") (pintype "passive"))
    )
    (net (code "76") (name "unconnected-(JP1-Pad40)") (class "Default")
      (node (ref "JP1") (pin "40") (pinfunction "40_40") (pintype "passive"))
    )
    (net (code "77") (name "unconnected-(JP2-Pad1)") (class "Default")
      (node (ref "JP2") (pin "1") (pinfunction "1_1") (pintype "passive"))
    )
    (net (code "78") (name "unconnected-(JP2-Pad2)") (class "Default")
      (node (ref "JP2") (pin "2") (pinfunction "2_2") (pintype "passive"))
    )
    (net (code "79") (name "unconnected-(JP2-Pad3)") (class "Default")
      (node (ref "JP2") (pin "3") (pinfunction "3_3") (pintype "passive"))
    )
    (net (code "80") (name "unconnected-(JP2-Pad4)") (class "Default")
      (node (ref "JP2") (pin "4") (pinfunction "4_4") (pintype "passive"))
    )
    (net (code "81") (name "unconnected-(JP2-Pad5)") (class "Default")
      (node (ref "JP2") (pin "5") (pinfunction "5_5") (pintype "passive"))
    )
    (net (code "82") (name "unconnected-(JP2-Pad6)") (class "Default")
      (node (ref "JP2") (pin "6") (pinfunction "6_6") (pintype "passive"))
    )
    (net (code "83") (name "unconnected-(JP2-Pad7)") (class "Default")
      (node (ref "JP2") (pin "7") (pinfunction "7_7") (pintype "passive"))
    )
    (net (code "84") (name "unconnected-(JP2-Pad12)") (class "Default")
      (node (ref "JP2") (pin "12") (pinfunction "12_12") (pintype "passive"))
    )
    (net (code "85") (name "unconnected-(JP2-Pad14)") (class "Default")
      (node (ref "JP2") (pin "14") (pinfunction "14_14") (pintype "passive"))
    )
    (net (code "86") (name "unconnected-(JP2-Pad16)") (class "Default")
      (node (ref "JP2") (pin "16") (pinfunction "16_16") (pintype "passive"))
    )
    (net (code "87") (name "unconnected-(JP2-Pad26)") (class "Default")
      (node (ref "JP2") (pin "26") (pinfunction "26_26") (pintype "passive"))
    )
    (net (code "88") (name "unconnected-(JP2-Pad28)") (class "Default")
      (node (ref "JP2") (pin "28") (pinfunction "28_28") (pintype "passive"))
    )
    (net (code "89") (name "unconnected-(JP2-Pad33)") (class "Default")
      (node (ref "JP2") (pin "33") (pinfunction "33_33") (pintype "passive"))
    )
    (net (code "90") (name "unconnected-(JP2-Pad34)") (class "Default")
      (node (ref "JP2") (pin "34") (pinfunction "34_34") (pintype "passive"))
    )
    (net (code "91") (name "unconnected-(JP2-Pad35)") (class "Default")
      (node (ref "JP2") (pin "35") (pinfunction "35_35") (pintype "passive"))
    )
    (net (code "92") (name "unconnected-(JP2-Pad36)") (class "Default")
      (node (ref "JP2") (pin "36") (pinfunction "36_36") (pintype "passive"))
    )
    (net (code "93") (name "unconnected-(JP2-Pad37)") (class "Default")
      (node (ref "JP2") (pin "37") (pinfunction "37_37") (pintype "passive"))
    )
    (net (code "94") (name "unconnected-(JP2-Pad38)") (class "Default")
      (node (ref "JP2") (pin "38") (pinfunction "38_38") (pintype "passive"))
    )
    (net (code "95") (name "unconnected-(JP2-Pad39)") (class "Default")
      (node (ref "JP2") (pin "39") (pinfunction "39_39") (pintype "passive"))
    )
    (net (code "96") (name "unconnected-(JP2-Pad40)") (class "Default")
      (node (ref "JP2") (pin "40") (pinfunction "40_40") (pintype "passive"))
    )
    (net (code "97") (name "unconnected-(JP3-Pad2)") (class "Default")
      (node (ref "JP3") (pin "2") (pinfunction "2_2") (pintype "passive"))
    )
    (net (code "98") (name "unconnected-(JP3-Pad3)") (class "Default")
      (node (ref "JP3") (pin "3") (pinfunction "3_3") (pintype "passive"))
    )
    (net (code "99") (name "unconnected-(JP3-Pad4)") (class "Default")
      (node (ref "JP3") (pin "4") (pinfunction "4_4") (pintype "passive"))
    )
    (net (code "100") (name "unconnected-(JP3-Pad6)") (class "Default")
      (node (ref "JP3") (pin "6") (pinfunction "6_6") (pintype "passive"))
    )
    (net (code "101") (name "unconnected-(JP3-Pad8)") (class "Default")
      (node (ref "JP3") (pin "8") (pinfunction "8_8") (pintype "passive"))
    )
    (net (code "102") (name "unconnected-(JP3-Pad9)") (class "Default")
      (node (ref "JP3") (pin "9") (pinfunction "9_9") (pintype "passive"))
    )
    (net (code "103") (name "unconnected-(JP3-Pad10)") (class "Default")
      (node (ref "JP3") (pin "10") (pinfunction "10_10") (pintype "passive"))
    )
    (net (code "104") (name "unconnected-(JP3-Pad11)") (class "Default")
      (node (ref "JP3") (pin "11") (pinfunction "11_11") (pintype "passive"))
    )
    (net (code "105") (name "unconnected-(JP3-Pad12)") (class "Default")
      (node (ref "JP3") (pin "12") (pinfunction "12_12") (pintype "passive"))
    )
    (net (code "106") (name "unconnected-(JP3-Pad13)") (class "Default")
      (node (ref "JP3") (pin "13") (pinfunction "13_13") (pintype "passive"))
    )
    (net (code "107") (name "unconnected-(JP3-Pad14)") (class "Default")
      (node (ref "JP3") (pin "14") (pinfunction "14_14") (pintype "passive"))
    )
    (net (code "108") (name "unconnected-(JP3-Pad15)") (class "Default")
      (node (ref "JP3") (pin "15") (pinfunction "15_15") (pintype "passive"))
    )
    (net (code "109") (name "unconnected-(JP3-Pad16)") (class "Default")
      (node (ref "JP3") (pin "16") (pinfunction "16_16") (pintype "passive"))
    )
    (net (code "110") (name "unconnected-(JP3-Pad17)") (class "Default")
      (node (ref "JP3") (pin "17") (pinfunction "17_17") (pintype "passive"))
    )
    (net (code "111") (name "unconnected-(JP3-Pad18)") (class "Default")
      (node (ref "JP3") (pin "18") (pinfunction "18_18") (pintype "passive"))
    )
    (net (code "112") (name "unconnected-(JP3-Pad19)") (class "Default")
      (node (ref "JP3") (pin "19") (pinfunction "19_19") (pintype "passive"))
    )
    (net (code "113") (name "unconnected-(JP3-Pad21)") (class "Default")
      (node (ref "JP3") (pin "21") (pinfunction "21_21") (pintype "passive"))
    )
    (net (code "114") (name "unconnected-(JP3-Pad22)") (class "Default")
      (node (ref "JP3") (pin "22") (pinfunction "22_22") (pintype "passive"))
    )
    (net (code "115") (name "unconnected-(JP3-Pad23)") (class "Default")
      (node (ref "JP3") (pin "23") (pinfunction "23_23") (pintype "passive"))
    )
    (net (code "116") (name "unconnected-(JP3-Pad24)") (class "Default")
      (node (ref "JP3") (pin "24") (pinfunction "24_24") (pintype "passive"))
    )
    (net (code "117") (name "unconnected-(JP3-Pad25)") (class "Default")
      (node (ref "JP3") (pin "25") (pinfunction "25_25") (pintype "passive"))
    )
    (net (code "118") (name "unconnected-(JP3-Pad26)") (class "Default")
      (node (ref "JP3") (pin "26") (pinfunction "26_26") (pintype "passive"))
    )
    (net (code "119") (name "unconnected-(JP3-Pad27)") (class "Default")
      (node (ref "JP3") (pin "27") (pinfunction "27_27") (pintype "passive"))
    )
    (net (code "120") (name "unconnected-(JP3-Pad28)") (class "Default")
      (node (ref "JP3") (pin "28") (pinfunction "28_28") (pintype "passive"))
    )
    (net (code "121") (name "unconnected-(JP3-Pad29)") (class "Default")
      (node (ref "JP3") (pin "29") (pinfunction "29_29") (pintype "passive"))
    )
    (net (code "122") (name "unconnected-(JP3-Pad30)") (class "Default")
      (node (ref "JP3") (pin "30") (pinfunction "30_30") (pintype "passive"))
    )
    (net (code "123") (name "unconnected-(JP3-Pad31)") (class "Default")
      (node (ref "JP3") (pin "31") (pinfunction "31_31") (pintype "passive"))
    )
    (net (code "124") (name "unconnected-(JP3-Pad32)") (class "Default")
      (node (ref "JP3") (pin "32") (pinfunction "32_32") (pintype "passive"))
    )
    (net (code "125") (name "unconnected-(JP3-Pad33)") (class "Default")
      (node (ref "JP3") (pin "33") (pinfunction "33_33") (pintype "passive"))
    )
    (net (code "126") (name "unconnected-(JP3-Pad34)") (class "Default")
      (node (ref "JP3") (pin "34") (pinfunction "34_34") (pintype "passive"))
    )
    (net (code "127") (name "unconnected-(JP3-Pad35)") (class "Default")
      (node (ref "JP3") (pin "35") (pinfunction "35_35") (pintype "passive"))
    )
    (net (code "128") (name "unconnected-(JP3-Pad36)") (class "Default")
      (node (ref "JP3") (pin "36") (pinfunction "36_36") (pintype "passive"))
    )
    (net (code "129") (name "unconnected-(JP3-Pad37)") (class "Default")
      (node (ref "JP3") (pin "37") (pinfunction "37_37") (pintype "passive"))
    )
    (net (code "130") (name "unconnected-(JP3-Pad38)") (class "Default")
      (node (ref "JP3") (pin "38") (pinfunction "38_38") (pintype "passive"))
    )
    (net (code "131") (name "unconnected-(JP3-Pad39)") (class "Default")
      (node (ref "JP3") (pin "39") (pinfunction "39_39") (pintype "passive"))
    )
    (net (code "132") (name "unconnected-(JP3-Pad40)") (class "Default")
      (node (ref "JP3") (pin "40") (pinfunction "40_40") (pintype "passive"))
    )
    (net (code "133") (name "unconnected-(U3-N{slash}C-Pad1)") (class "Default")
      (node (ref "U3") (pin "1") (pinfunction "N/C_1") (pintype "no_connect"))
    )
    (net (code "134") (name "unconnected-(USB-UART_1-Pad3)") (class "Default")
      (node (ref "USB-UART_1") (pin "3") (pinfunction "3_3") (pintype "passive"))
    )
    (net (code "135") (name "unconnected-(USB-UART_2-Pad1)") (class "Default")
      (node (ref "USB-UART_2") (pin "1") (pinfunction "1_1") (pintype "passive"))
    )
    (net (code "136") (name "unconnected-(USB-UART_2-Pad3)") (class "Default")
      (node (ref "USB-UART_2") (pin "3") (pinfunction "3_3") (pintype "passive"))
    )
    (net (code "137") (name "unconnected-(USB-UART_2-Pad4)") (class "Default")
      (node (ref "USB-UART_2") (pin "4") (pinfunction "4_4") (pintype "passive"))
    )
    (net (code "138") (name "unconnected-(VR1-CCW-Pad1)") (class "Default")
      (node (ref "VR1") (pin "1") (pinfunction "CCW_1") (pintype "bidirectional"))
    )
    (net (code "139") (name "unconnected-(VR2-CCW-Pad1)") (class "Default")
      (node (ref "VR2") (pin "1") (pinfunction "CCW_1") (pintype "bidirectional"))
    )
    (net (code "140") (name "unconnected-(VR3-CCW-Pad1)") (class "Default")
      (node (ref "VR3") (pin "1") (pinfunction "CCW_1") (pintype "bidirectional"))
    )
  )
)
